# Mini-Q.net
KiCad netlist of a schematic drawn in EAGLE
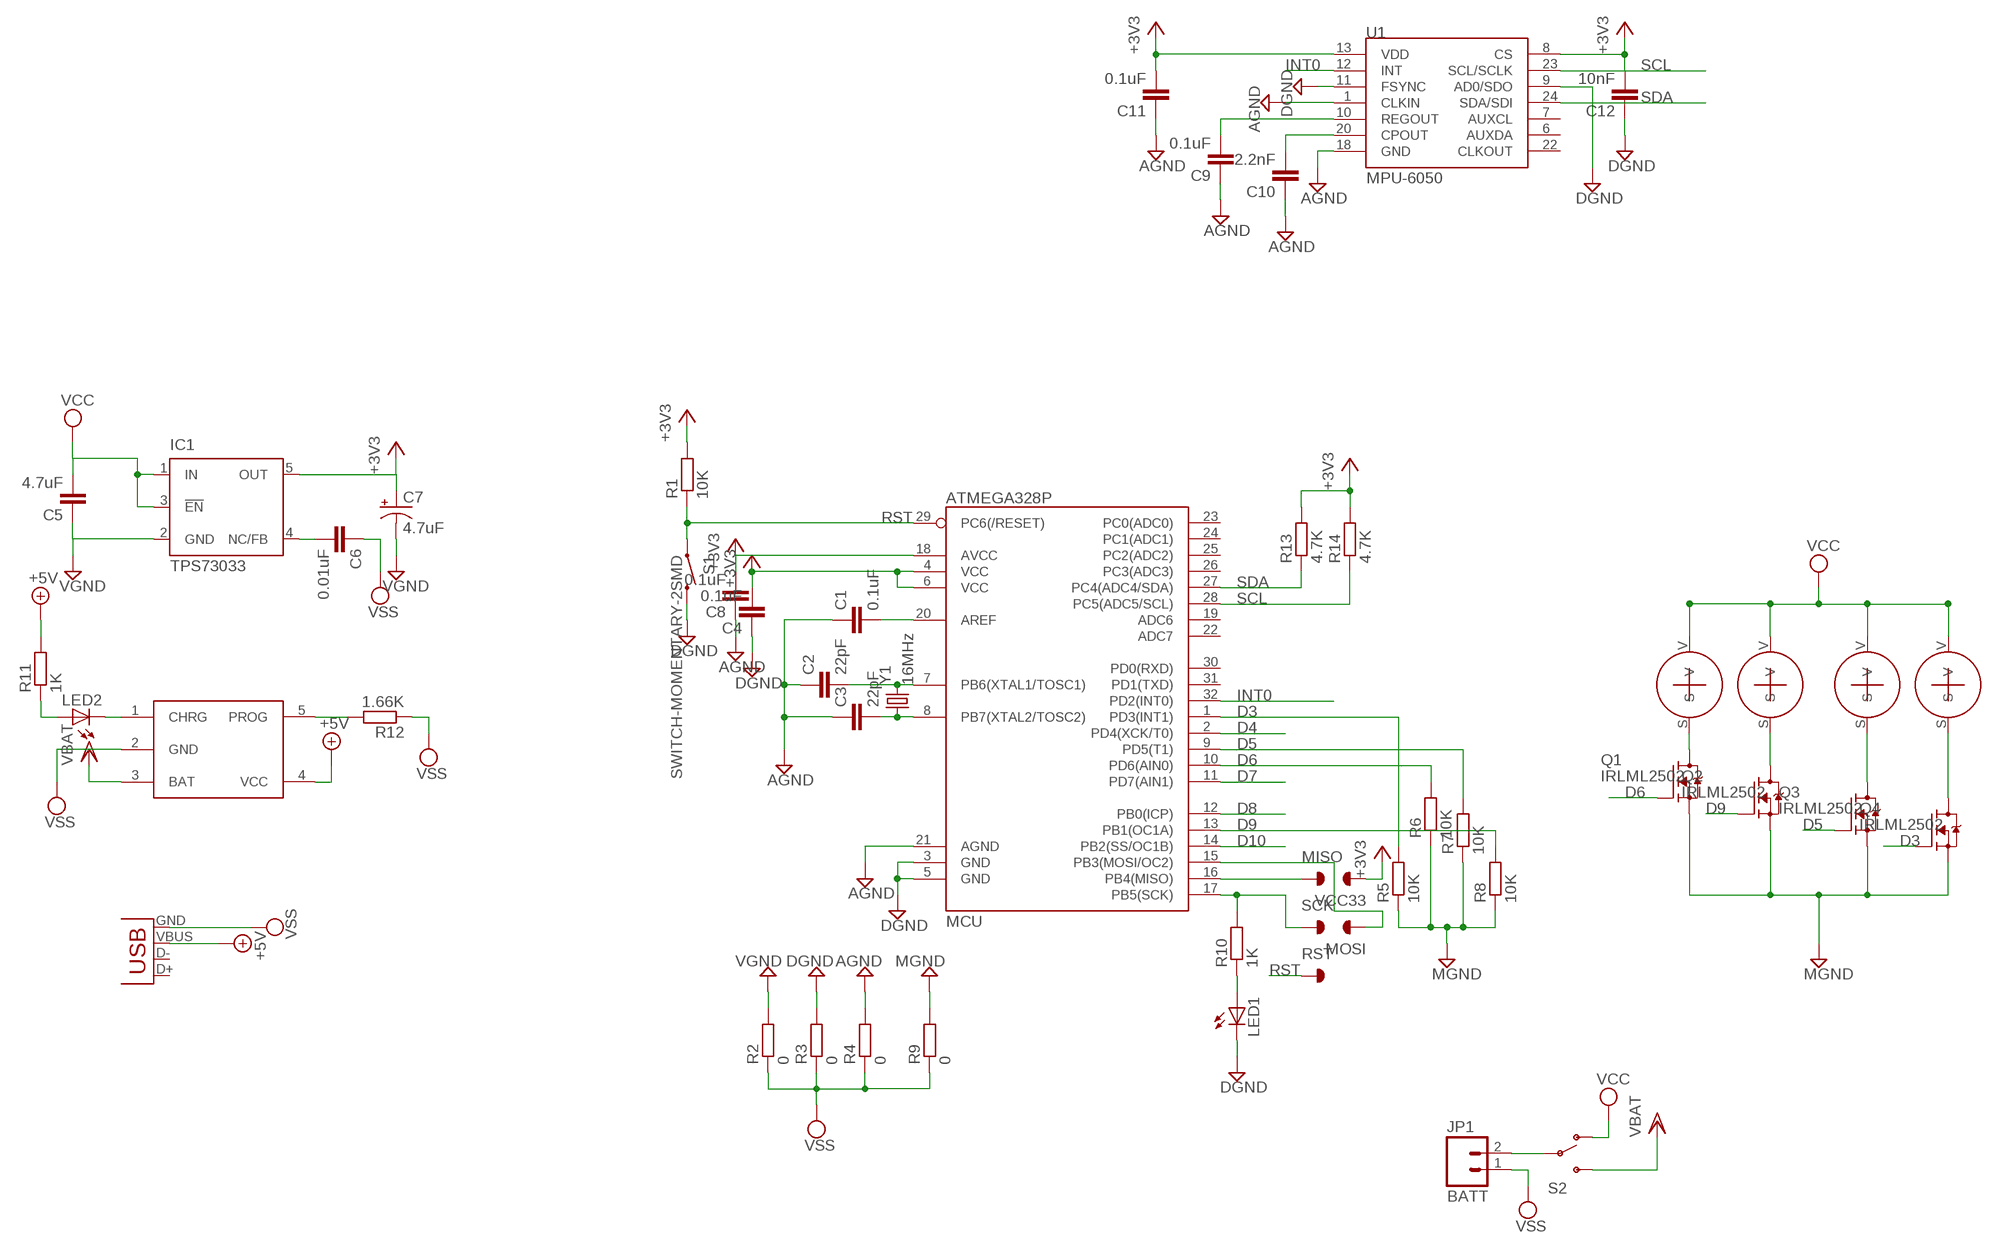
[diagram p0: schematic, sheet 1]

(export (version "E")
  (design (tool "Eeschema 10.0.6"))
  (components
    (comp (ref "C1")
      (value "0.1uF")
      (footprint "eagle-import:C0805")
      (libsource (lib "eagle-import") (part "C-EUC0805"))
    )
    (comp (ref "C2")
      (value "22pF")
      (footprint "eagle-import:C0603")
      (libsource (lib "eagle-import") (part "C-EUC0603"))
    )
    (comp (ref "C3")
      (value "22pF")
      (footprint "eagle-import:C0603")
      (libsource (lib "eagle-import") (part "C-EUC0603"))
    )
    (comp (ref "C4")
      (value "0.1uF")
      (footprint "eagle-import:C0805")
      (libsource (lib "eagle-import") (part "C-EUC0805"))
    )
    (comp (ref "C5")
      (value "4.7uF")
      (footprint "eagle-import:C0805")
      (libsource (lib "eagle-import") (part "C-EUC0805"))
    )
    (comp (ref "C6")
      (value "0.01uF")
      (footprint "eagle-import:C0805")
      (libsource (lib "eagle-import") (part "C-EUC0805"))
    )
    (comp (ref "C7")
      (value "4.7uF")
      (footprint "eagle-import:EIA3528")
      (libsource (lib "eagle-import") (part "CAP_POL3528"))
    )
    (comp (ref "C8")
      (value "0.1uF")
      (footprint "eagle-import:C0805")
      (libsource (lib "eagle-import") (part "C-EUC0805"))
    )
    (comp (ref "C9")
      (value "0.1uF")
      (footprint "eagle-import:C0805")
      (libsource (lib "eagle-import") (part "C-EUC0805"))
    )
    (comp (ref "C10")
      (value "2.2nF")
      (footprint "eagle-import:C0805")
      (libsource (lib "eagle-import") (part "C-EUC0805"))
    )
    (comp (ref "C11")
      (value "0.1uF")
      (footprint "eagle-import:C0805")
      (libsource (lib "eagle-import") (part "C-EUC0805"))
    )
    (comp (ref "C12")
      (value "10nF")
      (footprint "eagle-import:C0805")
      (libsource (lib "eagle-import") (part "C-EUC0805"))
    )
    (comp (ref "IC1")
      (value "TPS73033")
      (footprint "eagle-import:SOT23-DBV")
      (fields (field (name "MF") "TEXAS INSTRUMENTS") (field (name "MPN") "TPS77033DBVT"))
      (libsource (lib "eagle-import") (part "TPS77033"))
    )
    (comp (ref "JP1")
      (value "BATT")
      (footprint "eagle-import:1X02")
      (libsource (lib "eagle-import") (part "M02PTH"))
    )
    (comp (ref "JP2")
      (value "USBSMD")
      (footprint "eagle-import:USB-MINIB")
      (libsource (lib "eagle-import") (part "USBSMD"))
    )
    (comp (ref "LED1")
      (value "LEDSML0805")
      (footprint "eagle-import:SML0805")
      (libsource (lib "eagle-import") (part "LEDSML0805"))
    )
    (comp (ref "LED2")
      (value "LEDSML0805")
      (footprint "eagle-import:SML0805")
      (libsource (lib "eagle-import") (part "LEDSML0805"))
    )
    (comp (ref "MCU")
      (value "ATMEGA328P")
      (footprint "eagle-import:TQFP32-08")
      (libsource (lib "eagle-import") (part "ATMEGA328_SMT"))
    )
    (comp (ref "MISO")
      (value "xx")
      (footprint "eagle-import:POINT")
      (libsource (lib "eagle-import") (part "POINT"))
    )
    (comp (ref "MOSI")
      (value "xx")
      (footprint "eagle-import:POINT")
      (libsource (lib "eagle-import") (part "POINT"))
    )
    (comp (ref "Q1")
      (value "IRLML2502")
      (footprint "eagle-import:SOT23-3")
      (libsource (lib "eagle-import") (part "IRLML2502"))
    )
    (comp (ref "Q2")
      (value "IRLML2502")
      (footprint "eagle-import:SOT23-3")
      (libsource (lib "eagle-import") (part "IRLML2502"))
    )
    (comp (ref "Q3")
      (value "IRLML2502")
      (footprint "eagle-import:SOT23-3")
      (libsource (lib "eagle-import") (part "IRLML2502"))
    )
    (comp (ref "Q4")
      (value "IRLML2502")
      (footprint "eagle-import:SOT23-3")
      (libsource (lib "eagle-import") (part "IRLML2502"))
    )
    (comp (ref "R1")
      (value "10K")
      (footprint "eagle-import:R0805")
      (libsource (lib "eagle-import") (part "R-EU_R0805"))
    )
    (comp (ref "R2")
      (value "0")
      (footprint "eagle-import:R0805")
      (libsource (lib "eagle-import") (part "R-EU_R0805"))
    )
    (comp (ref "R3")
      (value "0")
      (footprint "eagle-import:R0805")
      (libsource (lib "eagle-import") (part "R-EU_R0805"))
    )
    (comp (ref "R4")
      (value "0")
      (footprint "eagle-import:R0805")
      (libsource (lib "eagle-import") (part "R-EU_R0805"))
    )
    (comp (ref "R5")
      (value "10K")
      (footprint "eagle-import:R0805")
      (libsource (lib "eagle-import") (part "R-EU_R0805"))
    )
    (comp (ref "R6")
      (value "10K")
      (footprint "eagle-import:R0805")
      (libsource (lib "eagle-import") (part "R-EU_R0805"))
    )
    (comp (ref "R7")
      (value "10K")
      (footprint "eagle-import:R0805")
      (libsource (lib "eagle-import") (part "R-EU_R0805"))
    )
    (comp (ref "R8")
      (value "10K")
      (footprint "eagle-import:R0805")
      (libsource (lib "eagle-import") (part "R-EU_R0805"))
    )
    (comp (ref "R9")
      (value "0")
      (footprint "eagle-import:R0805")
      (libsource (lib "eagle-import") (part "R-EU_R0805"))
    )
    (comp (ref "R10")
      (value "1K")
      (footprint "eagle-import:R0805")
      (libsource (lib "eagle-import") (part "R-EU_R0805"))
    )
    (comp (ref "R11")
      (value "1K")
      (footprint "eagle-import:R0805")
      (libsource (lib "eagle-import") (part "R-EU_R0805"))
    )
    (comp (ref "R12")
      (value "1.66K")
      (footprint "eagle-import:R0805")
      (libsource (lib "eagle-import") (part "R-EU_R0805"))
    )
    (comp (ref "R13")
      (value "4.7K")
      (footprint "eagle-import:R0805")
      (libsource (lib "eagle-import") (part "R-EU_R0805"))
    )
    (comp (ref "R14")
      (value "4.7K")
      (footprint "eagle-import:R0805")
      (libsource (lib "eagle-import") (part "R-EU_R0805"))
    )
    (comp (ref "RST")
      (value "xx")
      (footprint "eagle-import:POINT")
      (libsource (lib "eagle-import") (part "POINT"))
    )
    (comp (ref "S1")
      (value "SWITCH-MOMENTARY-2SMD")
      (footprint "eagle-import:TACTILE_SWITCH_SMD")
      (libsource (lib "eagle-import") (part "SWITCH-MOMENTARY-2SMD"))
    )
    (comp (ref "S2")
      (value "SWITCH-SPDT-SMD-A")
      (footprint "eagle-import:SWITCH-SPST-SMD-A")
      (libsource (lib "eagle-import") (part "SWITCH-SPDT-SMD-A"))
    )
    (comp (ref "SCK")
      (value "xx")
      (footprint "eagle-import:POINT")
      (libsource (lib "eagle-import") (part "POINT"))
    )
    (comp (ref "U$1")
      (value "MOTOR")
      (footprint "eagle-import:MOTOR")
      (libsource (lib "eagle-import") (part "MOTOR"))
    )
    (comp (ref "U$2")
      (value "MOTOR")
      (footprint "eagle-import:MOTOR")
      (libsource (lib "eagle-import") (part "MOTOR"))
    )
    (comp (ref "U$3")
      (value "MOTOR")
      (footprint "eagle-import:MOTOR")
      (libsource (lib "eagle-import") (part "MOTOR"))
    )
    (comp (ref "U$4")
      (value "MOTOR")
      (footprint "eagle-import:MOTOR")
      (libsource (lib "eagle-import") (part "MOTOR"))
    )
    (comp (ref "U$5")
      (value "TP4055")
      (footprint "eagle-import:SOT23-5")
      (libsource (lib "eagle-import") (part "TP4055"))
    )
    (comp (ref "U1")
      (value "MPU-6050")
      (footprint "eagle-import:QFN-24-TESTING")
      (libsource (lib "eagle-import") (part "MPU-6000QFN-24"))
    )
    (comp (ref "VCC33")
      (value "xx")
      (footprint "eagle-import:POINT")
      (libsource (lib "eagle-import") (part "POINT"))
    )
    (comp (ref "Y1")
      (value "16MHz")
      (footprint "eagle-import:HC49US")
      (libsource (lib "eagle-import") (part "CRYSTALHC49US"))
    )
  )
  (nets
    (net (code "1") (name "+3V3") (class "Default")
      (node (ref "C11") (pin "2") (pinfunction "2_2") (pintype "passive"))
      (node (ref "C12") (pin "2") (pinfunction "2_2") (pintype "passive"))
      (node (ref "C4") (pin "2") (pinfunction "2_2") (pintype "passive"))
      (node (ref "C7") (pin "A") (pinfunction "+_A") (pintype "passive"))
      (node (ref "C8") (pin "2") (pinfunction "2_2") (pintype "passive"))
      (node (ref "IC1") (pin "5") (pinfunction "OUT_5") (pintype "passive"))
      (node (ref "MCU") (pin "18") (pinfunction "AVCC_18") (pintype "bidirectional"))
      (node (ref "MCU") (pin "4") (pinfunction "VCC_4") (pintype "bidirectional"))
      (node (ref "MCU") (pin "6") (pinfunction "VCC_6") (pintype "bidirectional"))
      (node (ref "R1") (pin "2") (pinfunction "2_2") (pintype "passive"))
      (node (ref "R13") (pin "2") (pinfunction "2_2") (pintype "passive"))
      (node (ref "R14") (pin "2") (pinfunction "2_2") (pintype "passive"))
      (node (ref "U1") (pin "13") (pinfunction "VDD_13") (pintype "bidirectional"))
      (node (ref "U1") (pin "8") (pinfunction "CS_8") (pintype "bidirectional"))
      (node (ref "VCC33") (pin "P$1") (pinfunction "1_P$1") (pintype "bidirectional"))
    )
    (net (code "2") (name "+5V") (class "Default")
      (node (ref "JP2") (pin "VBUS") (pinfunction "VBUS_VBUS") (pintype "bidirectional"))
      (node (ref "R11") (pin "2") (pinfunction "2_2") (pintype "passive"))
      (node (ref "U$5") (pin "4") (pinfunction "VCC_4") (pintype "bidirectional"))
    )
    (net (code "3") (name "/D3") (class "Default")
      (node (ref "MCU") (pin "1") (pinfunction "PD3(INT1)_1") (pintype "bidirectional"))
      (node (ref "Q4") (pin "1") (pinfunction "G_1") (pintype "passive"))
      (node (ref "R5") (pin "2") (pinfunction "2_2") (pintype "passive"))
    )
    (net (code "4") (name "/D4") (class "Default")
      (node (ref "MCU") (pin "2") (pinfunction "PD4(XCK/T0)_2") (pintype "bidirectional"))
    )
    (net (code "5") (name "/D5") (class "Default")
      (node (ref "MCU") (pin "9") (pinfunction "PD5(T1)_9") (pintype "bidirectional"))
      (node (ref "Q3") (pin "1") (pinfunction "G_1") (pintype "passive"))
      (node (ref "R7") (pin "2") (pinfunction "2_2") (pintype "passive"))
    )
    (net (code "6") (name "/D6") (class "Default")
      (node (ref "MCU") (pin "10") (pinfunction "PD6(AIN0)_10") (pintype "bidirectional"))
      (node (ref "Q1") (pin "1") (pinfunction "G_1") (pintype "passive"))
      (node (ref "R6") (pin "2") (pinfunction "2_2") (pintype "passive"))
    )
    (net (code "7") (name "/D7") (class "Default")
      (node (ref "MCU") (pin "11") (pinfunction "PD7(AIN1)_11") (pintype "bidirectional"))
    )
    (net (code "8") (name "/D8") (class "Default")
      (node (ref "MCU") (pin "12") (pinfunction "PB0(ICP)_12") (pintype "bidirectional"))
    )
    (net (code "9") (name "/D9") (class "Default")
      (node (ref "MCU") (pin "13") (pinfunction "PB1(OC1A)_13") (pintype "bidirectional"))
      (node (ref "Q2") (pin "1") (pinfunction "G_1") (pintype "passive"))
      (node (ref "R8") (pin "2") (pinfunction "2_2") (pintype "passive"))
    )
    (net (code "10") (name "/D10") (class "Default")
      (node (ref "MCU") (pin "14") (pinfunction "PB2(SS/OC1B)_14") (pintype "bidirectional"))
    )
    (net (code "11") (name "/INT0") (class "Default")
      (node (ref "MCU") (pin "32") (pinfunction "PD2(INT0)_32") (pintype "bidirectional"))
      (node (ref "U1") (pin "12") (pinfunction "INT_12") (pintype "bidirectional"))
    )
    (net (code "12") (name "/RST") (class "Default")
      (node (ref "MCU") (pin "29") (pinfunction "PC6(/RESET)_29") (pintype "bidirectional"))
      (node (ref "R1") (pin "1") (pinfunction "1_1") (pintype "passive"))
      (node (ref "RST") (pin "P$1") (pinfunction "1_P$1") (pintype "bidirectional"))
      (node (ref "S1") (pin "1") (pinfunction "1_1") (pintype "passive"))
    )
    (net (code "13") (name "/SCL") (class "Default")
      (node (ref "MCU") (pin "28") (pinfunction "PC5(ADC5/SCL)_28") (pintype "bidirectional"))
      (node (ref "R14") (pin "1") (pinfunction "1_1") (pintype "passive"))
      (node (ref "U1") (pin "23") (pinfunction "SCL/SCLK_23") (pintype "bidirectional"))
    )
    (net (code "14") (name "/SDA") (class "Default")
      (node (ref "MCU") (pin "27") (pinfunction "PC4(ADC4/SDA)_27") (pintype "bidirectional"))
      (node (ref "R13") (pin "1") (pinfunction "1_1") (pintype "passive"))
      (node (ref "U1") (pin "24") (pinfunction "SDA/SDI_24") (pintype "bidirectional"))
    )
    (net (code "15") (name "AGND") (class "Default")
      (node (ref "C1") (pin "1") (pinfunction "1_1") (pintype "passive"))
      (node (ref "C10") (pin "1") (pinfunction "1_1") (pintype "passive"))
      (node (ref "C11") (pin "1") (pinfunction "1_1") (pintype "passive"))
      (node (ref "C2") (pin "1") (pinfunction "1_1") (pintype "passive"))
      (node (ref "C3") (pin "1") (pinfunction "1_1") (pintype "passive"))
      (node (ref "C8") (pin "1") (pinfunction "1_1") (pintype "passive"))
      (node (ref "C9") (pin "1") (pinfunction "1_1") (pintype "passive"))
      (node (ref "MCU") (pin "21") (pinfunction "AGND_21") (pintype "bidirectional"))
      (node (ref "R4") (pin "2") (pinfunction "2_2") (pintype "passive"))
      (node (ref "U1") (pin "1") (pinfunction "CLKIN_1") (pintype "bidirectional"))
      (node (ref "U1") (pin "18") (pinfunction "GND_18") (pintype "bidirectional"))
    )
    (net (code "16") (name "DGND") (class "Default")
      (node (ref "C12") (pin "1") (pinfunction "1_1") (pintype "passive"))
      (node (ref "C4") (pin "1") (pinfunction "1_1") (pintype "passive"))
      (node (ref "LED1") (pin "C") (pinfunction "C_C") (pintype "passive"))
      (node (ref "MCU") (pin "3") (pinfunction "GND_3") (pintype "bidirectional"))
      (node (ref "MCU") (pin "5") (pinfunction "GND_5") (pintype "bidirectional"))
      (node (ref "R3") (pin "2") (pinfunction "2_2") (pintype "passive"))
      (node (ref "S1") (pin "3") (pinfunction "2_3") (pintype "passive"))
      (node (ref "U1") (pin "11") (pinfunction "FSYNC_11") (pintype "bidirectional"))
      (node (ref "U1") (pin "9") (pinfunction "AD0/SDO_9") (pintype "bidirectional"))
    )
    (net (code "17") (name "MGND") (class "Default")
      (node (ref "Q1") (pin "2") (pinfunction "S_2") (pintype "passive"))
      (node (ref "Q2") (pin "2") (pinfunction "S_2") (pintype "passive"))
      (node (ref "Q3") (pin "2") (pinfunction "S_2") (pintype "passive"))
      (node (ref "Q4") (pin "2") (pinfunction "S_2") (pintype "passive"))
      (node (ref "R5") (pin "1") (pinfunction "1_1") (pintype "passive"))
      (node (ref "R6") (pin "1") (pinfunction "1_1") (pintype "passive"))
      (node (ref "R7") (pin "1") (pinfunction "1_1") (pintype "passive"))
      (node (ref "R8") (pin "1") (pinfunction "1_1") (pintype "passive"))
      (node (ref "R9") (pin "2") (pinfunction "2_2") (pintype "passive"))
    )
    (net (code "18") (name "Net-(IC1-NC{slash}FB)") (class "Default")
      (node (ref "C6") (pin "2") (pinfunction "2_2") (pintype "passive"))
      (node (ref "IC1") (pin "4") (pinfunction "NC/FB_4") (pintype "passive"))
    )
    (net (code "19") (name "Net-(LED1-PadA)") (class "Default")
      (node (ref "LED1") (pin "A") (pinfunction "A_A") (pintype "passive"))
      (node (ref "R10") (pin "1") (pinfunction "1_1") (pintype "passive"))
    )
    (net (code "20") (name "Net-(LED2-PadA)") (class "Default")
      (node (ref "LED2") (pin "A") (pinfunction "A_A") (pintype "passive"))
      (node (ref "R11") (pin "1") (pinfunction "1_1") (pintype "passive"))
    )
    (net (code "21") (name "Net-(MCU-AREF)") (class "Default")
      (node (ref "C1") (pin "2") (pinfunction "2_2") (pintype "passive"))
      (node (ref "MCU") (pin "20") (pinfunction "AREF_20") (pintype "bidirectional"))
    )
    (net (code "22") (name "Net-(MCU-PB3(MOSI{slash}OC2))") (class "Default")
      (node (ref "MCU") (pin "15") (pinfunction "PB3(MOSI/OC2)_15") (pintype "bidirectional"))
      (node (ref "MOSI") (pin "P$1") (pinfunction "1_P$1") (pintype "bidirectional"))
    )
    (net (code "23") (name "Net-(MCU-PB4(MISO))") (class "Default")
      (node (ref "MCU") (pin "16") (pinfunction "PB4(MISO)_16") (pintype "bidirectional"))
      (node (ref "MISO") (pin "P$1") (pinfunction "1_P$1") (pintype "bidirectional"))
    )
    (net (code "24") (name "Net-(MCU-PB5(SCK))") (class "Default")
      (node (ref "MCU") (pin "17") (pinfunction "PB5(SCK)_17") (pintype "bidirectional"))
      (node (ref "R10") (pin "2") (pinfunction "2_2") (pintype "passive"))
      (node (ref "SCK") (pin "P$1") (pinfunction "1_P$1") (pintype "bidirectional"))
    )
    (net (code "25") (name "Net-(MCU-PB6(XTAL1{slash}TOSC1))") (class "Default")
      (node (ref "C2") (pin "2") (pinfunction "2_2") (pintype "passive"))
      (node (ref "MCU") (pin "7") (pinfunction "PB6(XTAL1/TOSC1)_7") (pintype "bidirectional"))
      (node (ref "Y1") (pin "2") (pinfunction "2_2") (pintype "passive"))
    )
    (net (code "26") (name "Net-(MCU-PB7(XTAL2{slash}TOSC2))") (class "Default")
      (node (ref "C3") (pin "2") (pinfunction "2_2") (pintype "passive"))
      (node (ref "MCU") (pin "8") (pinfunction "PB7(XTAL2/TOSC2)_8") (pintype "bidirectional"))
      (node (ref "Y1") (pin "1") (pinfunction "1_1") (pintype "passive"))
    )
    (net (code "27") (name "Net-(Q1-D)") (class "Default")
      (node (ref "Q1") (pin "3") (pinfunction "D_3") (pintype "passive"))
      (node (ref "U$1") (pin "S") (pinfunction "S_S") (pintype "bidirectional"))
    )
    (net (code "28") (name "Net-(Q2-D)") (class "Default")
      (node (ref "Q2") (pin "3") (pinfunction "D_3") (pintype "passive"))
      (node (ref "U$2") (pin "S") (pinfunction "S_S") (pintype "bidirectional"))
    )
    (net (code "29") (name "Net-(Q3-D)") (class "Default")
      (node (ref "Q3") (pin "3") (pinfunction "D_3") (pintype "passive"))
      (node (ref "U$3") (pin "S") (pinfunction "S_S") (pintype "bidirectional"))
    )
    (net (code "30") (name "Net-(Q4-D)") (class "Default")
      (node (ref "Q4") (pin "3") (pinfunction "D_3") (pintype "passive"))
      (node (ref "U$4") (pin "S") (pinfunction "S_S") (pintype "bidirectional"))
    )
    (net (code "31") (name "Net-(S2-P)") (class "Default")
      (node (ref "JP1") (pin "2") (pinfunction "2_2") (pintype "passive"))
      (node (ref "S2") (pin "2") (pinfunction "P_2") (pintype "passive"))
    )
    (net (code "32") (name "Net-(U$5-CHRG)") (class "Default")
      (node (ref "LED2") (pin "C") (pinfunction "C_C") (pintype "passive"))
      (node (ref "U$5") (pin "1") (pinfunction "CHRG_1") (pintype "bidirectional"))
    )
    (net (code "33") (name "Net-(U$5-PROG)") (class "Default")
      (node (ref "R12") (pin "2") (pinfunction "2_2") (pintype "passive"))
      (node (ref "U$5") (pin "5") (pinfunction "PROG_5") (pintype "bidirectional"))
    )
    (net (code "34") (name "Net-(U1-CPOUT)") (class "Default")
      (node (ref "C10") (pin "2") (pinfunction "2_2") (pintype "passive"))
      (node (ref "U1") (pin "20") (pinfunction "CPOUT_20") (pintype "bidirectional"))
    )
    (net (code "35") (name "Net-(U1-REGOUT)") (class "Default")
      (node (ref "C9") (pin "2") (pinfunction "2_2") (pintype "passive"))
      (node (ref "U1") (pin "10") (pinfunction "REGOUT_10") (pintype "bidirectional"))
    )
    (net (code "36") (name "VBAT") (class "Default")
      (node (ref "S2") (pin "3") (pinfunction "S_3") (pintype "passive"))
      (node (ref "U$5") (pin "3") (pinfunction "BAT_3") (pintype "bidirectional"))
    )
    (net (code "37") (name "VCC") (class "Default")
      (node (ref "C5") (pin "2") (pinfunction "2_2") (pintype "passive"))
      (node (ref "IC1") (pin "1") (pinfunction "IN_1") (pintype "input"))
      (node (ref "IC1") (pin "3") (pinfunction "~{EN}_3") (pintype "input"))
      (node (ref "S2") (pin "1") (pinfunction "O_1") (pintype "passive"))
      (node (ref "U$1") (pin "V") (pinfunction "V_V") (pintype "bidirectional"))
      (node (ref "U$2") (pin "V") (pinfunction "V_V") (pintype "bidirectional"))
      (node (ref "U$3") (pin "V") (pinfunction "V_V") (pintype "bidirectional"))
      (node (ref "U$4") (pin "V") (pinfunction "V_V") (pintype "bidirectional"))
    )
    (net (code "38") (name "VGND") (class "Default")
      (node (ref "C5") (pin "1") (pinfunction "1_1") (pintype "passive"))
      (node (ref "C7") (pin "C") (pinfunction "-_C") (pintype "passive"))
      (node (ref "IC1") (pin "2") (pinfunction "GND_2") (pintype "power_in"))
      (node (ref "R2") (pin "2") (pinfunction "2_2") (pintype "passive"))
    )
    (net (code "39") (name "VSS") (class "Default")
      (node (ref "C6") (pin "1") (pinfunction "1_1") (pintype "passive"))
      (node (ref "JP1") (pin "1") (pinfunction "1_1") (pintype "passive"))
      (node (ref "JP2") (pin "GND") (pinfunction "GND_GND") (pintype "bidirectional"))
      (node (ref "R12") (pin "1") (pinfunction "1_1") (pintype "passive"))
      (node (ref "R2") (pin "1") (pinfunction "1_1") (pintype "passive"))
      (node (ref "R3") (pin "1") (pinfunction "1_1") (pintype "passive"))
      (node (ref "R4") (pin "1") (pinfunction "1_1") (pintype "passive"))
      (node (ref "R9") (pin "1") (pinfunction "1_1") (pintype "passive"))
      (node (ref "U$5") (pin "2") (pinfunction "GND_2") (pintype "bidirectional"))
    )
    (net (code "40") (name "unconnected-(JP2-PadD+)") (class "Default")
      (node (ref "JP2") (pin "D+") (pinfunction "D+_D+") (pintype "bidirectional"))
    )
    (net (code "41") (name "unconnected-(JP2-PadD-)") (class "Default")
      (node (ref "JP2") (pin "D-") (pinfunction "D-_D-") (pintype "bidirectional"))
    )
    (net (code "42") (name "unconnected-(MCU-ADC6-Pad19)") (class "Default")
      (node (ref "MCU") (pin "19") (pinfunction "ADC6_19") (pintype "bidirectional"))
    )
    (net (code "43") (name "unconnected-(MCU-ADC7-Pad22)") (class "Default")
      (node (ref "MCU") (pin "22") (pinfunction "ADC7_22") (pintype "bidirectional"))
    )
    (net (code "44") (name "unconnected-(MCU-PC0(ADC0)-Pad23)") (class "Default")
      (node (ref "MCU") (pin "23") (pinfunction "PC0(ADC0)_23") (pintype "bidirectional"))
    )
    (net (code "45") (name "unconnected-(MCU-PC1(ADC1)-Pad24)") (class "Default")
      (node (ref "MCU") (pin "24") (pinfunction "PC1(ADC1)_24") (pintype "bidirectional"))
    )
    (net (code "46") (name "unconnected-(MCU-PC2(ADC2)-Pad25)") (class "Default")
      (node (ref "MCU") (pin "25") (pinfunction "PC2(ADC2)_25") (pintype "bidirectional"))
    )
    (net (code "47") (name "unconnected-(MCU-PC3(ADC3)-Pad26)") (class "Default")
      (node (ref "MCU") (pin "26") (pinfunction "PC3(ADC3)_26") (pintype "bidirectional"))
    )
    (net (code "48") (name "unconnected-(MCU-PD0(RXD)-Pad30)") (class "Default")
      (node (ref "MCU") (pin "30") (pinfunction "PD0(RXD)_30") (pintype "bidirectional"))
    )
    (net (code "49") (name "unconnected-(MCU-PD1(TXD)-Pad31)") (class "Default")
      (node (ref "MCU") (pin "31") (pinfunction "PD1(TXD)_31") (pintype "bidirectional"))
    )
    (net (code "50") (name "unconnected-(U1-AUXCL-Pad7)") (class "Default")
      (node (ref "U1") (pin "7") (pinfunction "AUXCL_7") (pintype "bidirectional"))
    )
    (net (code "51") (name "unconnected-(U1-AUXDA-Pad6)") (class "Default")
      (node (ref "U1") (pin "6") (pinfunction "AUXDA_6") (pintype "bidirectional"))
    )
    (net (code "52") (name "unconnected-(U1-CLKOUT-Pad22)") (class "Default")
      (node (ref "U1") (pin "22") (pinfunction "CLKOUT_22") (pintype "bidirectional"))
    )
  )
)
